# pi-dmx.net
KiCad netlist of a schematic drawn in EAGLE
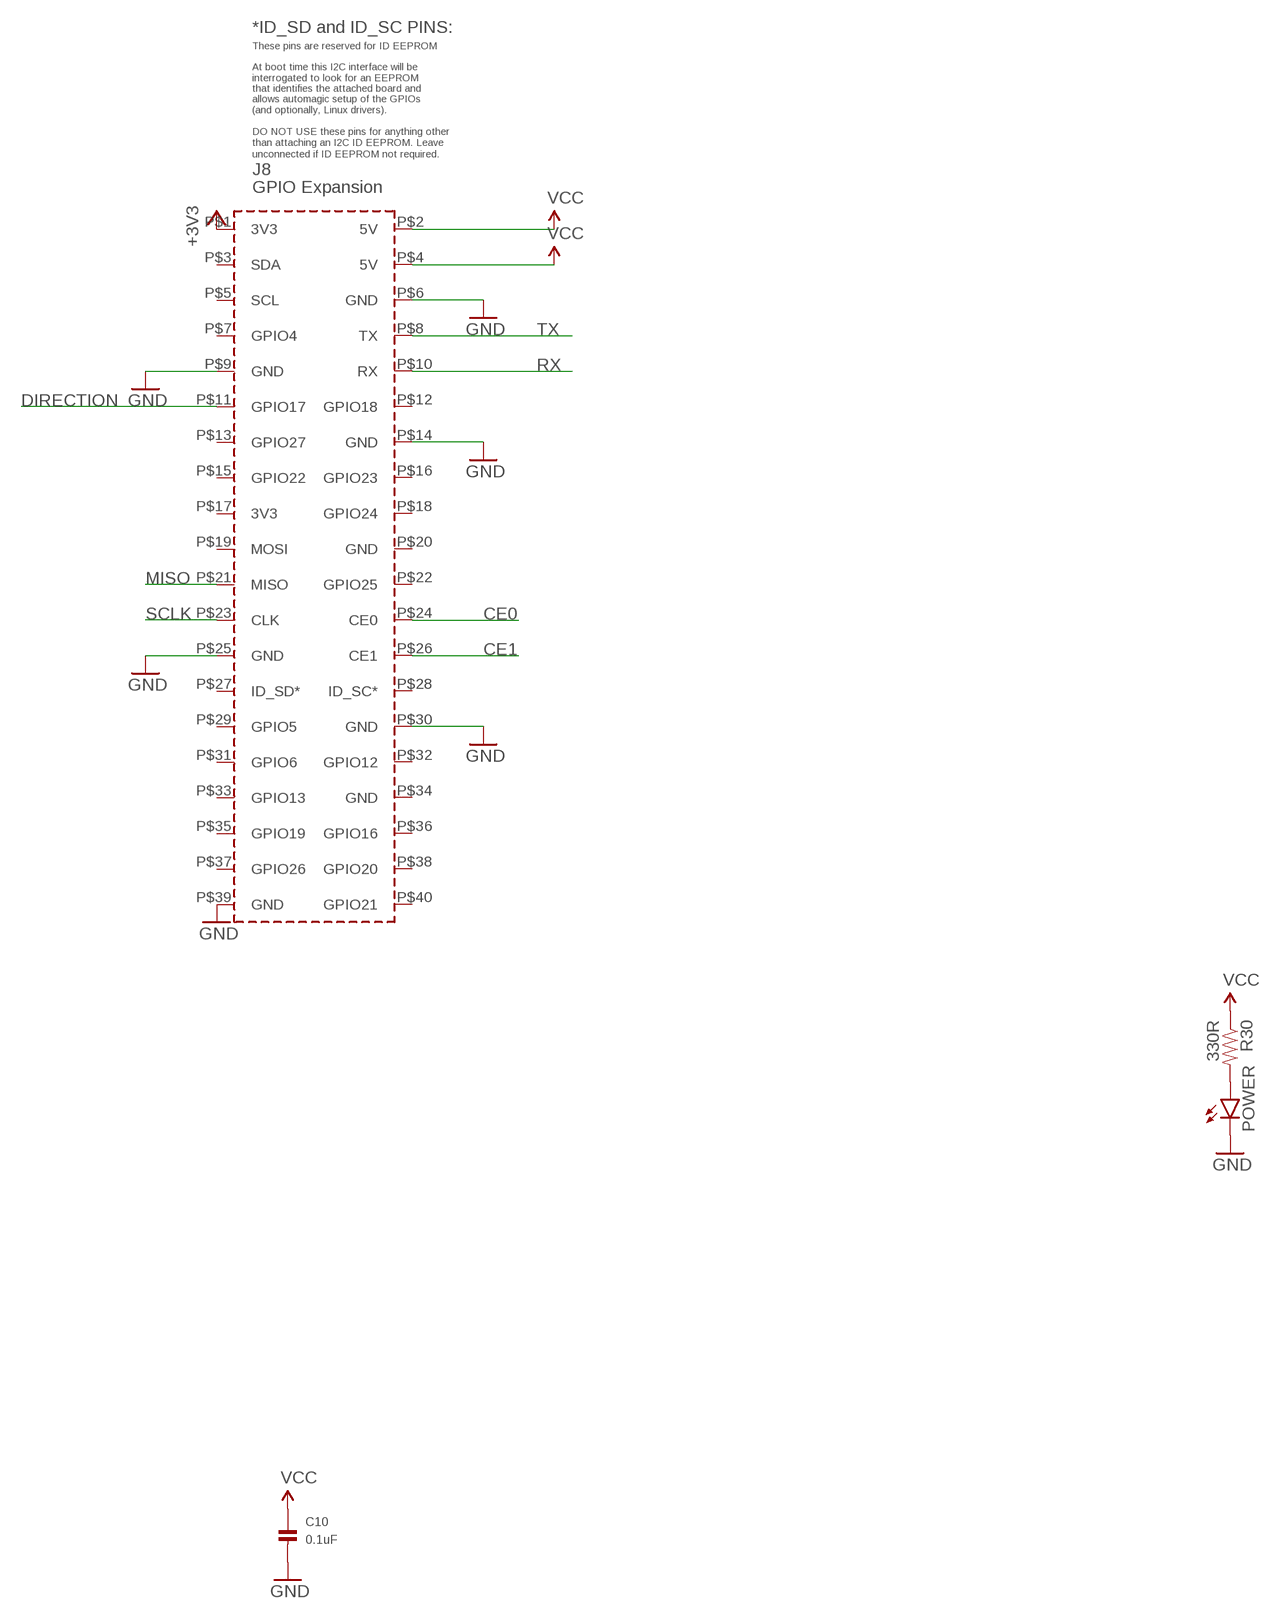
[diagram p0: schematic, sheet 1]
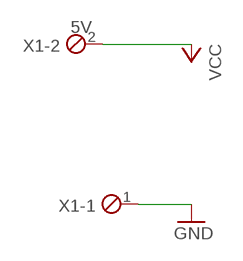
[diagram p1: schematic, sheet 2]
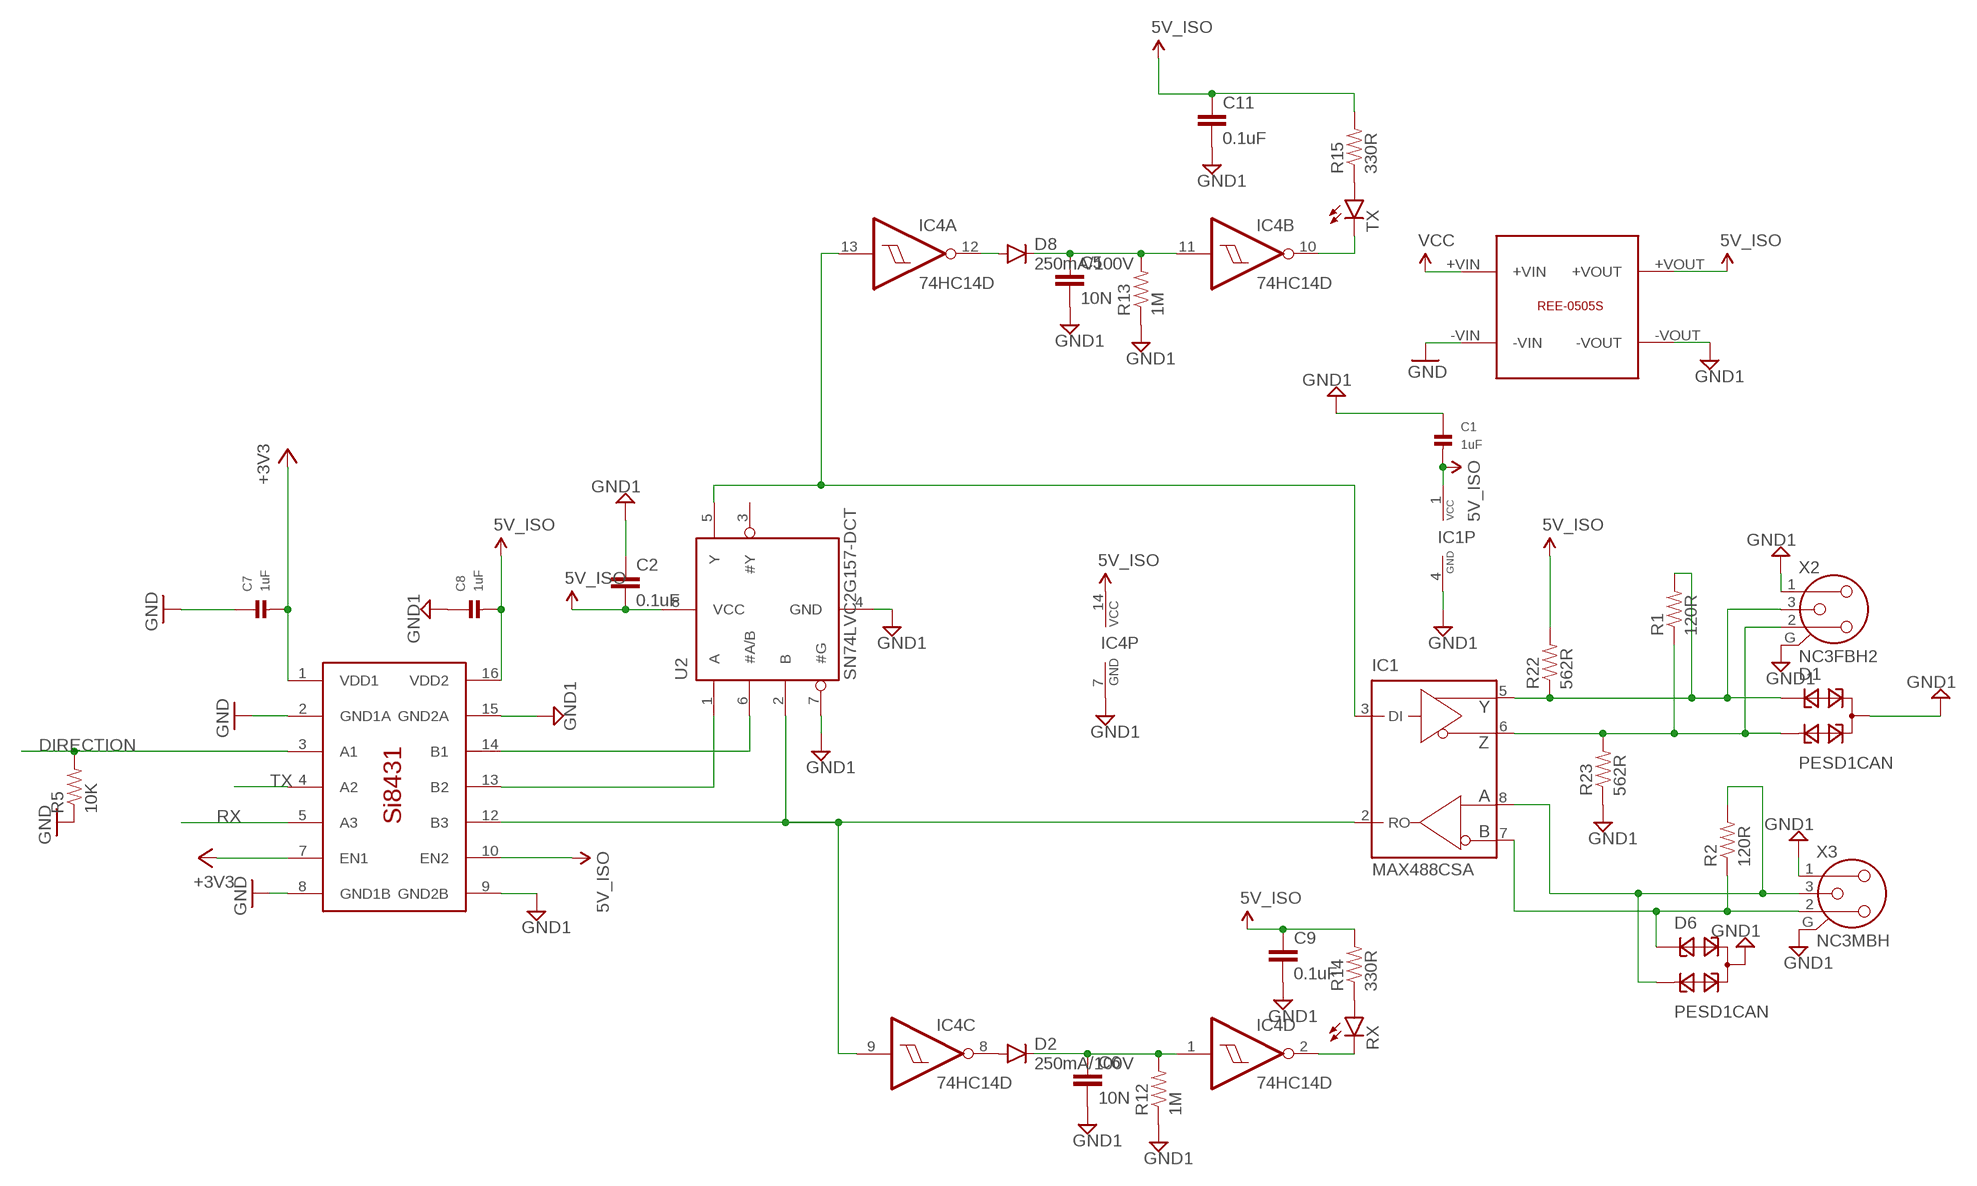
[diagram p2: schematic, sheet 4]
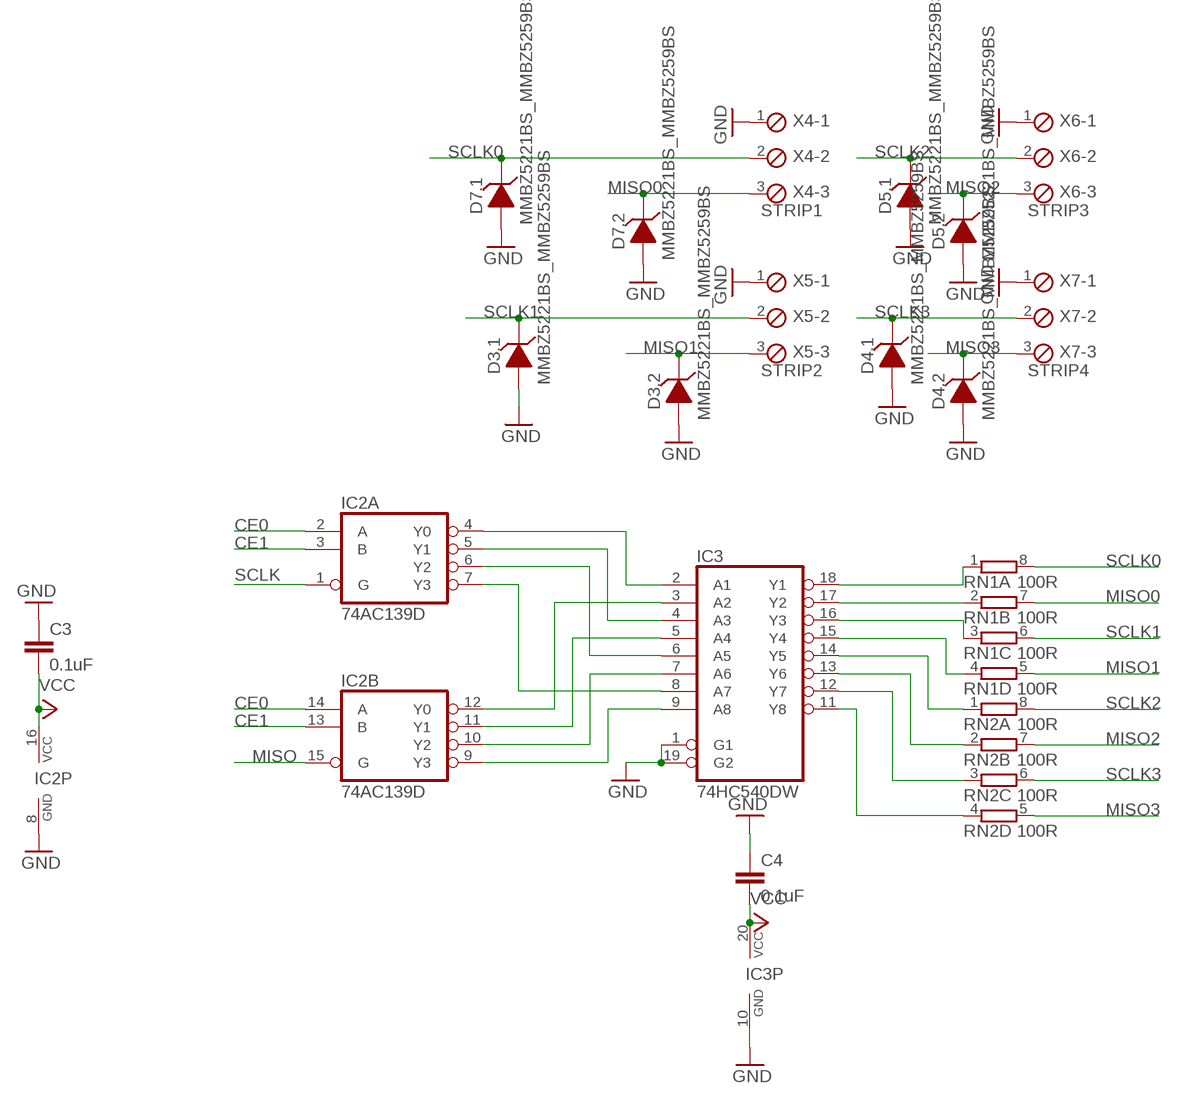
[diagram p3: schematic, sheet 6]

(export (version "E")
  (design (tool "Eeschema 10.0.6"))
  (components
    (comp (ref "C3")
      (value "0.1uF")
      (footprint "eagle-import:0603-CAP")
      (libsource (lib "eagle-import") (part "CAP0603-CAP"))
    )
    (comp (ref "C4")
      (value "0.1uF")
      (footprint "eagle-import:0603-CAP")
      (libsource (lib "eagle-import") (part "CAP0603-CAP"))
    )
    (comp (ref "D3")
      (value "MMBZ5221BS_MMBZ5259BS")
      (footprint "eagle-import:SOT363_PHILIPS")
      (libsource (lib "eagle-import") (part "MMBZ5221BS_MMBZ5259BS"))
    )
    (comp (ref "D4")
      (value "MMBZ5221BS_MMBZ5259BS")
      (footprint "eagle-import:SOT363_PHILIPS")
      (libsource (lib "eagle-import") (part "MMBZ5221BS_MMBZ5259BS"))
    )
    (comp (ref "D5")
      (value "MMBZ5221BS_MMBZ5259BS")
      (footprint "eagle-import:SOT363_PHILIPS")
      (libsource (lib "eagle-import") (part "MMBZ5221BS_MMBZ5259BS"))
    )
    (comp (ref "D7")
      (value "MMBZ5221BS_MMBZ5259BS")
      (footprint "eagle-import:SOT363_PHILIPS")
      (libsource (lib "eagle-import") (part "MMBZ5221BS_MMBZ5259BS"))
    )
    (comp (ref "IC2")
      (value "74AC139D")
      (footprint "eagle-import:SO16")
      (libsource (lib "eagle-import") (part "74139DAC"))
    )
    (comp (ref "IC3")
      (value "74HC540DW")
      (footprint "eagle-import:SO20W")
      (libsource (lib "eagle-import") (part "74540DWHC"))
    )
    (comp (ref "RN1")
      (value "100R")
      (footprint "eagle-import:EXBS8V")
      (libsource (lib "eagle-import") (part "4R-NEXBS8V"))
    )
    (comp (ref "RN2")
      (value "100R")
      (footprint "eagle-import:EXBS8V")
      (libsource (lib "eagle-import") (part "4R-NEXBS8V"))
    )
    (comp (ref "X4")
      (value "STRIP1")
      (footprint "eagle-import:3POL254")
      (libsource (lib "eagle-import") (part "MPT3"))
    )
    (comp (ref "X5")
      (value "STRIP2")
      (footprint "eagle-import:3POL254")
      (libsource (lib "eagle-import") (part "MPT3"))
    )
    (comp (ref "X6")
      (value "STRIP3")
      (footprint "eagle-import:3POL254")
      (libsource (lib "eagle-import") (part "MPT3"))
    )
    (comp (ref "X7")
      (value "STRIP4")
      (footprint "eagle-import:3POL254")
      (libsource (lib "eagle-import") (part "MPT3"))
    )
    (comp (ref "C1")
      (value "1uF")
      (footprint "eagle-import:0805")
      (libsource (lib "eagle-import") (part "CAP_CERAMIC0805"))
    )
    (comp (ref "C2")
      (value "0.1uF")
      (footprint "eagle-import:0603-CAP")
      (libsource (lib "eagle-import") (part "SparkFun-Passives_CAP0603-CAP"))
    )
    (comp (ref "C5")
      (value "10N")
      (footprint "eagle-import:0603-CAP")
      (libsource (lib "eagle-import") (part "CAP0603-CAP"))
    )
    (comp (ref "C6")
      (value "10N")
      (footprint "eagle-import:0603-CAP")
      (libsource (lib "eagle-import") (part "CAP0603-CAP"))
    )
    (comp (ref "C7")
      (value "1uF")
      (footprint "eagle-import:0805")
      (libsource (lib "eagle-import") (part "CAP_CERAMIC0805"))
    )
    (comp (ref "C8")
      (value "1uF")
      (footprint "eagle-import:0805")
      (libsource (lib "eagle-import") (part "CAP_CERAMIC0805"))
    )
    (comp (ref "C9")
      (value "0.1uF")
      (footprint "eagle-import:0603-CAP")
      (libsource (lib "eagle-import") (part "CAP0603-CAP"))
    )
    (comp (ref "C11")
      (value "0.1uF")
      (footprint "eagle-import:0603-CAP")
      (libsource (lib "eagle-import") (part "CAP0603-CAP"))
    )
    (comp (ref "D1")
      (value "PESD1CAN")
      (footprint "eagle-import:SOT23")
      (libsource (lib "eagle-import") (part "PESD1CAN"))
    )
    (comp (ref "D2")
      (value "250mA/100V")
      (footprint "eagle-import:SOD-323")
      (libsource (lib "eagle-import") (part "DIODEBAS16"))
    )
    (comp (ref "D6")
      (value "PESD1CAN")
      (footprint "eagle-import:SOT23")
      (libsource (lib "eagle-import") (part "PESD1CAN"))
    )
    (comp (ref "D8")
      (value "250mA/100V")
      (footprint "eagle-import:SOD-323")
      (libsource (lib "eagle-import") (part "DIODEBAS16"))
    )
    (comp (ref "IC1")
      (value "MAX488CSA")
      (footprint "eagle-import:SO08")
      (fields (field (name "MF") "MAXIM"))
      (libsource (lib "eagle-import") (part "MAX488CSA"))
    )
    (comp (ref "IC4")
      (value "74HC14D")
      (footprint "eagle-import:SO14")
      (libsource (lib "eagle-import") (part "7414DHC"))
    )
    (comp (ref "R1")
      (value "120R")
      (footprint "eagle-import:1206")
      (libsource (lib "eagle-import") (part "SparkFun-Resistors_RESISTOR1206"))
    )
    (comp (ref "R2")
      (value "120R")
      (footprint "eagle-import:1206")
      (libsource (lib "eagle-import") (part "SparkFun-Resistors_RESISTOR1206"))
    )
    (comp (ref "R5")
      (value "10K")
      (footprint "eagle-import:0603-RES")
      (libsource (lib "eagle-import") (part "RESISTOR0603-RES"))
    )
    (comp (ref "R12")
      (value "1M")
      (footprint "eagle-import:0603-RES")
      (libsource (lib "eagle-import") (part "SparkFun-Resistors_RESISTOR0603-RES"))
    )
    (comp (ref "R13")
      (value "1M")
      (footprint "eagle-import:0603-RES")
      (libsource (lib "eagle-import") (part "SparkFun-Resistors_RESISTOR0603-RES"))
    )
    (comp (ref "R14")
      (value "330R")
      (footprint "eagle-import:0603-RES")
      (libsource (lib "eagle-import") (part "SparkFun-Resistors_RESISTOR0603-RES"))
    )
    (comp (ref "R15")
      (value "330R")
      (footprint "eagle-import:0603-RES")
      (libsource (lib "eagle-import") (part "SparkFun-Resistors_RESISTOR0603-RES"))
    )
    (comp (ref "R22")
      (value "562R")
      (footprint "eagle-import:0603-RES")
      (libsource (lib "eagle-import") (part "RESISTOR0603-RES"))
    )
    (comp (ref "R23")
      (value "562R")
      (footprint "eagle-import:0603-RES")
      (libsource (lib "eagle-import") (part "RESISTOR0603-RES"))
    )
    (comp (ref "RX")
      (value "LED1206")
      (footprint "eagle-import:LED-1206")
      (libsource (lib "eagle-import") (part "LED1206"))
    )
    (comp (ref "TX")
      (value "LED1206")
      (footprint "eagle-import:LED-1206")
      (libsource (lib "eagle-import") (part "LED1206"))
    )
    (comp (ref "U$6")
      (value "REE-0505S")
      (footprint "eagle-import:REE-0505S")
      (libsource (lib "eagle-import") (part "REE-0505S"))
    )
    (comp (ref "U$8")
      (value "SI8431")
      (footprint "eagle-import:SO16")
      (libsource (lib "eagle-import") (part "SI8431"))
    )
    (comp (ref "U2")
      (value "SN74LVC2G157-DCT")
      (footprint "eagle-import:SSOP8")
      (libsource (lib "eagle-import") (part "SN74LVC2G157-DCT"))
    )
    (comp (ref "X2")
      (value "NC3FBH2")
      (footprint "eagle-import:NC3FBH2")
      (libsource (lib "eagle-import") (part "NC3FBH2"))
    )
    (comp (ref "X3")
      (value "NC3MBH")
      (footprint "eagle-import:NC3MBH")
      (fields (field (name "MF") "NEUTRIK"))
      (libsource (lib "eagle-import") (part "NC3MBH"))
    )
    (comp (ref "C10")
      (value "0.1uF")
      (footprint "eagle-import:0805")
      (libsource (lib "eagle-import") (part "CAP_CERAMIC0805"))
    )
    (comp (ref "PCB1")
      (value "RPI2")
      (footprint "eagle-import:RPI2")
      (libsource (lib "eagle-import") (part "RPI2"))
    )
    (comp (ref "POWER")
      (value "LED1206")
      (footprint "eagle-import:LED-1206")
      (libsource (lib "eagle-import") (part "LED1206"))
    )
    (comp (ref "R30")
      (value "330R")
      (footprint "eagle-import:0603-RES")
      (libsource (lib "eagle-import") (part "RESISTOR0603-RES"))
    )
    (comp (ref "X1")
      (value "5V")
      (footprint "eagle-import:2POL254")
      (libsource (lib "eagle-import") (part "MPT2"))
    )
  )
  (nets
    (net (code "1") (name "+3V3") (class "Default")
      (node (ref "C7") (pin "2") (pinfunction "P$2_2") (pintype "passive"))
      (node (ref "PCB1") (pin "P$1") (pinfunction "3V3_P$1") (pintype "bidirectional"))
      (node (ref "U$8") (pin "1") (pinfunction "VDD1_1") (pintype "bidirectional"))
      (node (ref "U$8") (pin "7") (pinfunction "EN1_7") (pintype "bidirectional"))
    )
    (net (code "2") (name "5V") (class "Default")
      (node (ref "C1") (pin "2") (pinfunction "P$2_2") (pintype "passive"))
      (node (ref "C11") (pin "1") (pinfunction "1_1") (pintype "passive"))
      (node (ref "C2") (pin "2") (pinfunction "2_2") (pintype "passive"))
      (node (ref "C8") (pin "2") (pinfunction "P$2_2") (pintype "passive"))
      (node (ref "C9") (pin "1") (pinfunction "1_1") (pintype "passive"))
      (node (ref "IC1") (pin "1") (pinfunction "VCC_1") (pintype "power_in"))
      (node (ref "IC4") (pin "14") (pinfunction "VCC_14") (pintype "power_in"))
      (node (ref "R14") (pin "2") (pinfunction "2_2") (pintype "passive"))
      (node (ref "R15") (pin "2") (pinfunction "2_2") (pintype "passive"))
      (node (ref "R22") (pin "2") (pinfunction "2_2") (pintype "passive"))
      (node (ref "U$6") (pin "+VOUT") (pinfunction "+VOUT_+VOUT") (pintype "bidirectional"))
      (node (ref "U$8") (pin "10") (pinfunction "EN2_10") (pintype "bidirectional"))
      (node (ref "U$8") (pin "16") (pinfunction "VDD2_16") (pintype "bidirectional"))
      (node (ref "U2") (pin "8") (pinfunction "VCC_8") (pintype "power_in"))
    )
    (net (code "3") (name "CE0") (class "Default")
      (node (ref "IC2") (pin "14") (pinfunction "A_14") (pintype "input"))
      (node (ref "IC2") (pin "2") (pinfunction "A_2") (pintype "input"))
      (node (ref "PCB1") (pin "P$24") (pinfunction "CE0_P$24") (pintype "bidirectional"))
    )
    (net (code "4") (name "CE1") (class "Default")
      (node (ref "IC2") (pin "13") (pinfunction "B_13") (pintype "input"))
      (node (ref "IC2") (pin "3") (pinfunction "B_3") (pintype "input"))
      (node (ref "PCB1") (pin "P$26") (pinfunction "CE1_P$26") (pintype "bidirectional"))
    )
    (net (code "5") (name "DIRECTION") (class "Default")
      (node (ref "PCB1") (pin "P$11") (pinfunction "GPIO17_P$11") (pintype "bidirectional"))
      (node (ref "R5") (pin "2") (pinfunction "2_2") (pintype "passive"))
      (node (ref "U$8") (pin "3") (pinfunction "A1_3") (pintype "bidirectional"))
    )
    (net (code "6") (name "GND") (class "Default")
      (node (ref "C10") (pin "2") (pinfunction "P$2_2") (pintype "passive"))
      (node (ref "C3") (pin "1") (pinfunction "1_1") (pintype "passive"))
      (node (ref "C4") (pin "1") (pinfunction "1_1") (pintype "passive"))
      (node (ref "C7") (pin "1") (pinfunction "P$1_1") (pintype "passive"))
      (node (ref "D3") (pin "1") (pinfunction "A_1") (pintype "passive"))
      (node (ref "D3") (pin "4") (pinfunction "A_4") (pintype "passive"))
      (node (ref "D4") (pin "1") (pinfunction "A_1") (pintype "passive"))
      (node (ref "D4") (pin "4") (pinfunction "A_4") (pintype "passive"))
      (node (ref "D5") (pin "1") (pinfunction "A_1") (pintype "passive"))
      (node (ref "D5") (pin "4") (pinfunction "A_4") (pintype "passive"))
      (node (ref "D7") (pin "1") (pinfunction "A_1") (pintype "passive"))
      (node (ref "D7") (pin "4") (pinfunction "A_4") (pintype "passive"))
      (node (ref "IC2") (pin "8") (pinfunction "GND_8") (pintype "power_in"))
      (node (ref "IC3") (pin "1") (pinfunction "G1_1") (pintype "input"))
      (node (ref "IC3") (pin "10") (pinfunction "GND_10") (pintype "power_in"))
      (node (ref "IC3") (pin "19") (pinfunction "G2_19") (pintype "input"))
      (node (ref "PCB1") (pin "P$14") (pinfunction "GND_P$14") (pintype "bidirectional"))
      (node (ref "PCB1") (pin "P$25") (pinfunction "GND_P$25") (pintype "bidirectional"))
      (node (ref "PCB1") (pin "P$30") (pinfunction "GND_P$30") (pintype "bidirectional"))
      (node (ref "PCB1") (pin "P$39") (pinfunction "GND_P$39") (pintype "bidirectional"))
      (node (ref "PCB1") (pin "P$6") (pinfunction "GND_P$6") (pintype "bidirectional"))
      (node (ref "PCB1") (pin "P$9") (pinfunction "GND_P$9") (pintype "bidirectional"))
      (node (ref "POWER") (pin "C") (pinfunction "C_C") (pintype "passive"))
      (node (ref "R5") (pin "1") (pinfunction "1_1") (pintype "passive"))
      (node (ref "U$6") (pin "-VIN") (pinfunction "-VIN_-VIN") (pintype "bidirectional"))
      (node (ref "U$8") (pin "2") (pinfunction "GND1A_2") (pintype "bidirectional"))
      (node (ref "U$8") (pin "8") (pinfunction "GND1B_8") (pintype "bidirectional"))
      (node (ref "X1") (pin "1") (pinfunction "1_1") (pintype "passive"))
      (node (ref "X4") (pin "1") (pinfunction "1_1") (pintype "passive"))
      (node (ref "X5") (pin "1") (pinfunction "1_1") (pintype "passive"))
      (node (ref "X6") (pin "1") (pinfunction "1_1") (pintype "passive"))
      (node (ref "X7") (pin "1") (pinfunction "1_1") (pintype "passive"))
    )
    (net (code "7") (name "GND1") (class "Default")
      (node (ref "C1") (pin "1") (pinfunction "P$1_1") (pintype "passive"))
      (node (ref "C11") (pin "2") (pinfunction "2_2") (pintype "passive"))
      (node (ref "C2") (pin "1") (pinfunction "1_1") (pintype "passive"))
      (node (ref "C5") (pin "2") (pinfunction "2_2") (pintype "passive"))
      (node (ref "C6") (pin "2") (pinfunction "2_2") (pintype "passive"))
      (node (ref "C8") (pin "1") (pinfunction "P$1_1") (pintype "passive"))
      (node (ref "C9") (pin "2") (pinfunction "2_2") (pintype "passive"))
      (node (ref "D1") (pin "3") (pinfunction "3_3") (pintype "passive"))
      (node (ref "D6") (pin "3") (pinfunction "3_3") (pintype "passive"))
      (node (ref "IC1") (pin "4") (pinfunction "GND_4") (pintype "power_in"))
      (node (ref "IC4") (pin "7") (pinfunction "GND_7") (pintype "power_in"))
      (node (ref "R12") (pin "1") (pinfunction "1_1") (pintype "passive"))
      (node (ref "R13") (pin "1") (pinfunction "1_1") (pintype "passive"))
      (node (ref "R23") (pin "1") (pinfunction "1_1") (pintype "passive"))
      (node (ref "U$6") (pin "-VOUT") (pinfunction "-VOUT_-VOUT") (pintype "bidirectional"))
      (node (ref "U$8") (pin "15") (pinfunction "GND2A_15") (pintype "bidirectional"))
      (node (ref "U$8") (pin "9") (pinfunction "GND2B_9") (pintype "bidirectional"))
      (node (ref "U2") (pin "4") (pinfunction "GND_4") (pintype "power_in"))
      (node (ref "U2") (pin "7") (pinfunction "#G_7") (pintype "input"))
      (node (ref "X2") (pin "1") (pinfunction "1_1") (pintype "passive"))
      (node (ref "X2") (pin "G") (pinfunction "G_G") (pintype "passive"))
      (node (ref "X3") (pin "1") (pinfunction "1_1") (pintype "passive"))
      (node (ref "X3") (pin "G") (pinfunction "G_G") (pintype "passive"))
    )
    (net (code "8") (name "MISO") (class "Default")
      (node (ref "IC2") (pin "15") (pinfunction "G_15") (pintype "input"))
      (node (ref "PCB1") (pin "P$21") (pinfunction "MISO_P$21") (pintype "bidirectional"))
    )
    (net (code "9") (name "MISO0") (class "Default")
      (node (ref "D7") (pin "3") (pinfunction "C_3") (pintype "passive"))
      (node (ref "RN1") (pin "7") (pinfunction "2_7") (pintype "passive"))
      (node (ref "X4") (pin "3") (pinfunction "1_3") (pintype "passive"))
    )
    (net (code "10") (name "MISO1") (class "Default")
      (node (ref "D3") (pin "3") (pinfunction "C_3") (pintype "passive"))
      (node (ref "RN1") (pin "5") (pinfunction "2_5") (pintype "passive"))
      (node (ref "X5") (pin "3") (pinfunction "1_3") (pintype "passive"))
    )
    (net (code "11") (name "MISO2") (class "Default")
      (node (ref "D5") (pin "3") (pinfunction "C_3") (pintype "passive"))
      (node (ref "RN2") (pin "7") (pinfunction "2_7") (pintype "passive"))
      (node (ref "X6") (pin "3") (pinfunction "1_3") (pintype "passive"))
    )
    (net (code "12") (name "MISO3") (class "Default")
      (node (ref "D4") (pin "3") (pinfunction "C_3") (pintype "passive"))
      (node (ref "RN2") (pin "5") (pinfunction "2_5") (pintype "passive"))
      (node (ref "X7") (pin "3") (pinfunction "1_3") (pintype "passive"))
    )
    (net (code "13") (name "Net-(IC1A-A)") (class "Default")
      (node (ref "D6") (pin "2") (pinfunction "2_2") (pintype "passive"))
      (node (ref "IC1") (pin "8") (pinfunction "A_8") (pintype "input"))
      (node (ref "R2") (pin "2") (pinfunction "2_2") (pintype "passive"))
      (node (ref "X3") (pin "3") (pinfunction "3_3") (pintype "passive"))
    )
    (net (code "14") (name "Net-(IC1A-B)") (class "Default")
      (node (ref "D6") (pin "1") (pinfunction "1_1") (pintype "passive"))
      (node (ref "IC1") (pin "7") (pinfunction "B_7") (pintype "input"))
      (node (ref "R2") (pin "1") (pinfunction "1_1") (pintype "passive"))
      (node (ref "X3") (pin "2") (pinfunction "2_2") (pintype "passive"))
    )
    (net (code "15") (name "Net-(IC1A-DI)") (class "Default")
      (node (ref "IC1") (pin "3") (pinfunction "DI_3") (pintype "input"))
      (node (ref "IC4") (pin "13") (pinfunction "I_13") (pintype "input"))
      (node (ref "U2") (pin "5") (pinfunction "Y_5") (pintype "output"))
    )
    (net (code "16") (name "Net-(IC1A-RO)") (class "Default")
      (node (ref "IC1") (pin "2") (pinfunction "RO_2") (pintype "output"))
      (node (ref "IC4") (pin "9") (pinfunction "I_9") (pintype "input"))
      (node (ref "U$8") (pin "12") (pinfunction "B3_12") (pintype "bidirectional"))
      (node (ref "U2") (pin "2") (pinfunction "B_2") (pintype "input"))
    )
    (net (code "17") (name "Net-(IC1A-Y)") (class "Default")
      (node (ref "D1") (pin "1") (pinfunction "1_1") (pintype "passive"))
      (node (ref "IC1") (pin "5") (pinfunction "Y_5") (pintype "output"))
      (node (ref "R1") (pin "2") (pinfunction "2_2") (pintype "passive"))
      (node (ref "R22") (pin "1") (pinfunction "1_1") (pintype "passive"))
      (node (ref "X2") (pin "3") (pinfunction "3_3") (pintype "passive"))
    )
    (net (code "18") (name "Net-(IC1A-Z)") (class "Default")
      (node (ref "D1") (pin "2") (pinfunction "2_2") (pintype "passive"))
      (node (ref "IC1") (pin "6") (pinfunction "Z_6") (pintype "output"))
      (node (ref "R1") (pin "1") (pinfunction "1_1") (pintype "passive"))
      (node (ref "R23") (pin "2") (pinfunction "2_2") (pintype "passive"))
      (node (ref "X2") (pin "2") (pinfunction "2_2") (pintype "passive"))
    )
    (net (code "19") (name "Net-(IC2A-Y0)") (class "Default")
      (node (ref "IC2") (pin "4") (pinfunction "Y0_4") (pintype "output"))
      (node (ref "IC3") (pin "2") (pinfunction "A1_2") (pintype "input"))
    )
    (net (code "20") (name "Net-(IC2A-Y1)") (class "Default")
      (node (ref "IC2") (pin "5") (pinfunction "Y1_5") (pintype "output"))
      (node (ref "IC3") (pin "4") (pinfunction "A3_4") (pintype "input"))
    )
    (net (code "21") (name "Net-(IC2A-Y2)") (class "Default")
      (node (ref "IC2") (pin "6") (pinfunction "Y2_6") (pintype "output"))
      (node (ref "IC3") (pin "6") (pinfunction "A5_6") (pintype "input"))
    )
    (net (code "22") (name "Net-(IC2A-Y3)") (class "Default")
      (node (ref "IC2") (pin "7") (pinfunction "Y3_7") (pintype "output"))
      (node (ref "IC3") (pin "8") (pinfunction "A7_8") (pintype "input"))
    )
    (net (code "23") (name "Net-(IC2B-Y0)") (class "Default")
      (node (ref "IC2") (pin "12") (pinfunction "Y0_12") (pintype "output"))
      (node (ref "IC3") (pin "3") (pinfunction "A2_3") (pintype "input"))
    )
    (net (code "24") (name "Net-(IC2B-Y1)") (class "Default")
      (node (ref "IC2") (pin "11") (pinfunction "Y1_11") (pintype "output"))
      (node (ref "IC3") (pin "5") (pinfunction "A4_5") (pintype "input"))
    )
    (net (code "25") (name "Net-(IC2B-Y2)") (class "Default")
      (node (ref "IC2") (pin "10") (pinfunction "Y2_10") (pintype "output"))
      (node (ref "IC3") (pin "7") (pinfunction "A6_7") (pintype "input"))
    )
    (net (code "26") (name "Net-(IC2B-Y3)") (class "Default")
      (node (ref "IC2") (pin "9") (pinfunction "Y3_9") (pintype "output"))
      (node (ref "IC3") (pin "9") (pinfunction "A8_9") (pintype "input"))
    )
    (net (code "27") (name "Net-(IC3A-Y1)") (class "Default")
      (node (ref "IC3") (pin "18") (pinfunction "Y1_18") (pintype "tri_state"))
      (node (ref "RN1") (pin "1") (pinfunction "1_1") (pintype "passive"))
    )
    (net (code "28") (name "Net-(IC3A-Y2)") (class "Default")
      (node (ref "IC3") (pin "17") (pinfunction "Y2_17") (pintype "tri_state"))
      (node (ref "RN1") (pin "2") (pinfunction "1_2") (pintype "passive"))
    )
    (net (code "29") (name "Net-(IC3A-Y3)") (class "Default")
      (node (ref "IC3") (pin "16") (pinfunction "Y3_16") (pintype "tri_state"))
      (node (ref "RN1") (pin "3") (pinfunction "1_3") (pintype "passive"))
    )
    (net (code "30") (name "Net-(IC3A-Y4)") (class "Default")
      (node (ref "IC3") (pin "15") (pinfunction "Y4_15") (pintype "tri_state"))
      (node (ref "RN1") (pin "4") (pinfunction "1_4") (pintype "passive"))
    )
    (net (code "31") (name "Net-(IC3A-Y5)") (class "Default")
      (node (ref "IC3") (pin "14") (pinfunction "Y5_14") (pintype "tri_state"))
      (node (ref "RN2") (pin "1") (pinfunction "1_1") (pintype "passive"))
    )
    (net (code "32") (name "Net-(IC3A-Y6)") (class "Default")
      (node (ref "IC3") (pin "13") (pinfunction "Y6_13") (pintype "tri_state"))
      (node (ref "RN2") (pin "2") (pinfunction "1_2") (pintype "passive"))
    )
    (net (code "33") (name "Net-(IC3A-Y7)") (class "Default")
      (node (ref "IC3") (pin "12") (pinfunction "Y7_12") (pintype "tri_state"))
      (node (ref "RN2") (pin "3") (pinfunction "1_3") (pintype "passive"))
    )
    (net (code "34") (name "Net-(IC3A-Y8)") (class "Default")
      (node (ref "IC3") (pin "11") (pinfunction "Y8_11") (pintype "tri_state"))
      (node (ref "RN2") (pin "4") (pinfunction "1_4") (pintype "passive"))
    )
    (net (code "35") (name "Net-(IC4A-O)") (class "Default")
      (node (ref "D8") (pin "A") (pinfunction "A_A") (pintype "passive"))
      (node (ref "IC4") (pin "12") (pinfunction "O_12") (pintype "output"))
    )
    (net (code "36") (name "Net-(IC4B-I)") (class "Default")
      (node (ref "C5") (pin "1") (pinfunction "1_1") (pintype "passive"))
      (node (ref "D8") (pin "C") (pinfunction "C_C") (pintype "passive"))
      (node (ref "IC4") (pin "11") (pinfunction "I_11") (pintype "input"))
      (node (ref "R13") (pin "2") (pinfunction "2_2") (pintype "passive"))
    )
    (net (code "37") (name "Net-(IC4B-O)") (class "Default")
      (node (ref "IC4") (pin "10") (pinfunction "O_10") (pintype "output"))
      (node (ref "TX") (pin "C") (pinfunction "C_C") (pintype "passive"))
    )
    (net (code "38") (name "Net-(IC4C-O)") (class "Default")
      (node (ref "D2") (pin "A") (pinfunction "A_A") (pintype "passive"))
      (node (ref "IC4") (pin "8") (pinfunction "O_8") (pintype "output"))
    )
    (net (code "39") (name "Net-(IC4D-I)") (class "Default")
      (node (ref "C6") (pin "1") (pinfunction "1_1") (pintype "passive"))
      (node (ref "D2") (pin "C") (pinfunction "C_C") (pintype "passive"))
      (node (ref "IC4") (pin "1") (pinfunction "I_1") (pintype "input"))
      (node (ref "R12") (pin "2") (pinfunction "2_2") (pintype "passive"))
    )
    (net (code "40") (name "Net-(IC4D-O)") (class "Default")
      (node (ref "IC4") (pin "2") (pinfunction "O_2") (pintype "output"))
      (node (ref "RX") (pin "C") (pinfunction "C_C") (pintype "passive"))
    )
    (net (code "41") (name "Net-(POWER-PadA)") (class "Default")
      (node (ref "POWER") (pin "A") (pinfunction "A_A") (pintype "passive"))
      (node (ref "R30") (pin "2") (pinfunction "2_2") (pintype "passive"))
    )
    (net (code "42") (name "Net-(R14-Pad1)") (class "Default")
      (node (ref "R14") (pin "1") (pinfunction "1_1") (pintype "passive"))
      (node (ref "RX") (pin "A") (pinfunction "A_A") (pintype "passive"))
    )
    (net (code "43") (name "Net-(R15-Pad1)") (class "Default")
      (node (ref "R15") (pin "1") (pinfunction "1_1") (pintype "passive"))
      (node (ref "TX") (pin "A") (pinfunction "A_A") (pintype "passive"))
    )
    (net (code "44") (name "Net-(U$8-B1)") (class "Default")
      (node (ref "U$8") (pin "14") (pinfunction "B1_14") (pintype "bidirectional"))
      (node (ref "U2") (pin "6") (pinfunction "#A/B_6") (pintype "input"))
    )
    (net (code "45") (name "Net-(U$8-B2)") (class "Default")
      (node (ref "U$8") (pin "13") (pinfunction "B2_13") (pintype "bidirectional"))
      (node (ref "U2") (pin "1") (pinfunction "A_1") (pintype "input"))
    )
    (net (code "46") (name "RX") (class "Default")
      (node (ref "PCB1") (pin "P$10") (pinfunction "RX_P$10") (pintype "bidirectional"))
      (node (ref "U$8") (pin "5") (pinfunction "A3_5") (pintype "bidirectional"))
    )
    (net (code "47") (name "SCLK") (class "Default")
      (node (ref "IC2") (pin "1") (pinfunction "G_1") (pintype "input"))
      (node (ref "PCB1") (pin "P$23") (pinfunction "CLK_P$23") (pintype "bidirectional"))
    )
    (net (code "48") (name "SCLK0") (class "Default")
      (node (ref "D7") (pin "6") (pinfunction "C_6") (pintype "passive"))
      (node (ref "RN1") (pin "8") (pinfunction "2_8") (pintype "passive"))
      (node (ref "X4") (pin "2") (pinfunction "1_2") (pintype "passive"))
    )
    (net (code "49") (name "SCLK1") (class "Default")
      (node (ref "D3") (pin "6") (pinfunction "C_6") (pintype "passive"))
      (node (ref "RN1") (pin "6") (pinfunction "2_6") (pintype "passive"))
      (node (ref "X5") (pin "2") (pinfunction "1_2") (pintype "passive"))
    )
    (net (code "50") (name "SCLK2") (class "Default")
      (node (ref "D5") (pin "6") (pinfunction "C_6") (pintype "passive"))
      (node (ref "RN2") (pin "8") (pinfunction "2_8") (pintype "passive"))
      (node (ref "X6") (pin "2") (pinfunction "1_2") (pintype "passive"))
    )
    (net (code "51") (name "SCLK3") (class "Default")
      (node (ref "D4") (pin "6") (pinfunction "C_6") (pintype "passive"))
      (node (ref "RN2") (pin "6") (pinfunction "2_6") (pintype "passive"))
      (node (ref "X7") (pin "2") (pinfunction "1_2") (pintype "passive"))
    )
    (net (code "52") (name "TX") (class "Default")
      (node (ref "PCB1") (pin "P$8") (pinfunction "TX_P$8") (pintype "bidirectional"))
      (node (ref "U$8") (pin "4") (pinfunction "A2_4") (pintype "bidirectional"))
    )
    (net (code "53") (name "VCC") (class "Default")
      (node (ref "C10") (pin "1") (pinfunction "P$1_1") (pintype "passive"))
      (node (ref "C3") (pin "2") (pinfunction "2_2") (pintype "passive"))
      (node (ref "C4") (pin "2") (pinfunction "2_2") (pintype "passive"))
      (node (ref "IC2") (pin "16") (pinfunction "VCC_16") (pintype "power_in"))
      (node (ref "IC3") (pin "20") (pinfunction "VCC_20") (pintype "power_in"))
      (node (ref "PCB1") (pin "P$2") (pinfunction "5V_P$2") (pintype "bidirectional"))
      (node (ref "PCB1") (pin "P$4") (pinfunction "5V_P$4") (pintype "bidirectional"))
      (node (ref "R30") (pin "1") (pinfunction "1_1") (pintype "passive"))
      (node (ref "U$6") (pin "+VIN") (pinfunction "+VIN_+VIN") (pintype "bidirectional"))
      (node (ref "X1") (pin "2") (pinfunction "1_2") (pintype "passive"))
    )
    (net (code "54") (name "unconnected-(PCB1-3V3-PadP$17)") (class "Default")
      (node (ref "PCB1") (pin "P$17") (pinfunction "3V3_P$17") (pintype "bidirectional"))
    )
    (net (code "55") (name "unconnected-(PCB1-GND-PadP$20)") (class "Default")
      (node (ref "PCB1") (pin "P$20") (pinfunction "GND_P$20") (pintype "bidirectional"))
    )
    (net (code "56") (name "unconnected-(PCB1-GND-PadP$34)") (class "Default")
      (node (ref "PCB1") (pin "P$34") (pinfunction "GND_P$34") (pintype "bidirectional"))
    )
    (net (code "57") (name "unconnected-(PCB1-GPIO4-PadP$7)") (class "Default")
      (node (ref "PCB1") (pin "P$7") (pinfunction "GPIO4_P$7") (pintype "bidirectional"))
    )
    (net (code "58") (name "unconnected-(PCB1-GPIO5-PadP$29)") (class "Default")
      (node (ref "PCB1") (pin "P$29") (pinfunction "GPIO5_P$29") (pintype "bidirectional"))
    )
    (net (code "59") (name "unconnected-(PCB1-GPIO6-PadP$31)") (class "Default")
      (node (ref "PCB1") (pin "P$31") (pinfunction "GPIO6_P$31") (pintype "bidirectional"))
    )
    (net (code "60") (name "unconnected-(PCB1-GPIO12-PadP$32)") (class "Default")
      (node (ref "PCB1") (pin "P$32") (pinfunction "GPIO12_P$32") (pintype "bidirectional"))
    )
    (net (code "61") (name "unconnected-(PCB1-GPIO13-PadP$33)") (class "Default")
      (node (ref "PCB1") (pin "P$33") (pinfunction "GPIO13_P$33") (pintype "bidirectional"))
    )
    (net (code "62") (name "unconnected-(PCB1-GPIO16-PadP$36)") (class "Default")
      (node (ref "PCB1") (pin "P$36") (pinfunction "GPIO16_P$36") (pintype "bidirectional"))
    )
    (net (code "63") (name "unconnected-(PCB1-GPIO18-PadP$12)") (class "Default")
      (node (ref "PCB1") (pin "P$12") (pinfunction "GPIO18_P$12") (pintype "bidirectional"))
    )
    (net (code "64") (name "unconnected-(PCB1-GPIO19-PadP$35)") (class "Default")
      (node (ref "PCB1") (pin "P$35") (pinfunction "GPIO19_P$35") (pintype "bidirectional"))
    )
    (net (code "65") (name "unconnected-(PCB1-GPIO20-PadP$38)") (class "Default")
      (node (ref "PCB1") (pin "P$38") (pinfunction "GPIO20_P$38") (pintype "bidirectional"))
    )
    (net (code "66") (name "unconnected-(PCB1-GPIO21-PadP$40)") (class "Default")
      (node (ref "PCB1") (pin "P$40") (pinfunction "GPIO21_P$40") (pintype "bidirectional"))
    )
    (net (code "67") (name "unconnected-(PCB1-GPIO22-PadP$15)") (class "Default")
      (node (ref "PCB1") (pin "P$15") (pinfunction "GPIO22_P$15") (pintype "bidirectional"))
    )
    (net (code "68") (name "unconnected-(PCB1-GPIO23-PadP$16)") (class "Default")
      (node (ref "PCB1") (pin "P$16") (pinfunction "GPIO23_P$16") (pintype "bidirectional"))
    )
    (net (code "69") (name "unconnected-(PCB1-GPIO24-PadP$18)") (class "Default")
      (node (ref "PCB1") (pin "P$18") (pinfunction "GPIO24_P$18") (pintype "bidirectional"))
    )
    (net (code "70") (name "unconnected-(PCB1-GPIO25-PadP$22)") (class "Default")
      (node (ref "PCB1") (pin "P$22") (pinfunction "GPIO25_P$22") (pintype "bidirectional"))
    )
    (net (code "71") (name "unconnected-(PCB1-GPIO26-PadP$37)") (class "Default")
      (node (ref "PCB1") (pin "P$37") (pinfunction "GPIO26_P$37") (pintype "bidirectional"))
    )
    (net (code "72") (name "unconnected-(PCB1-GPIO27-PadP$13)") (class "Default")
      (node (ref "PCB1") (pin "P$13") (pinfunction "GPIO27_P$13") (pintype "bidirectional"))
    )
    (net (code "73") (name "unconnected-(PCB1-ID_SC*-PadP$28)") (class "Default")
      (node (ref "PCB1") (pin "P$28") (pinfunction "ID_SC*_P$28") (pintype "bidirectional"))
    )
    (net (code "74") (name "unconnected-(PCB1-ID_SD*-PadP$27)") (class "Default")
      (node (ref "PCB1") (pin "P$27") (pinfunction "ID_SD*_P$27") (pintype "bidirectional"))
    )
    (net (code "75") (name "unconnected-(PCB1-MOSI-PadP$19)") (class "Default")
      (node (ref "PCB1") (pin "P$19") (pinfunction "MOSI_P$19") (pintype "bidirectional"))
    )
    (net (code "76") (name "unconnected-(PCB1-SCL-PadP$5)") (class "Default")
      (node (ref "PCB1") (pin "P$5") (pinfunction "SCL_P$5") (pintype "bidirectional"))
    )
    (net (code "77") (name "unconnected-(PCB1-SDA-PadP$3)") (class "Default")
      (node (ref "PCB1") (pin "P$3") (pinfunction "SDA_P$3") (pintype "bidirectional"))
    )
    (net (code "78") (name "unconnected-(U2-#Y-Pad3)") (class "Default")
      (node (ref "U2") (pin "3") (pinfunction "#Y_3") (pintype "output"))
    )
  )
)
